# airu-schematic-pi.net
KiCad netlist of a schematic drawn in EAGLE
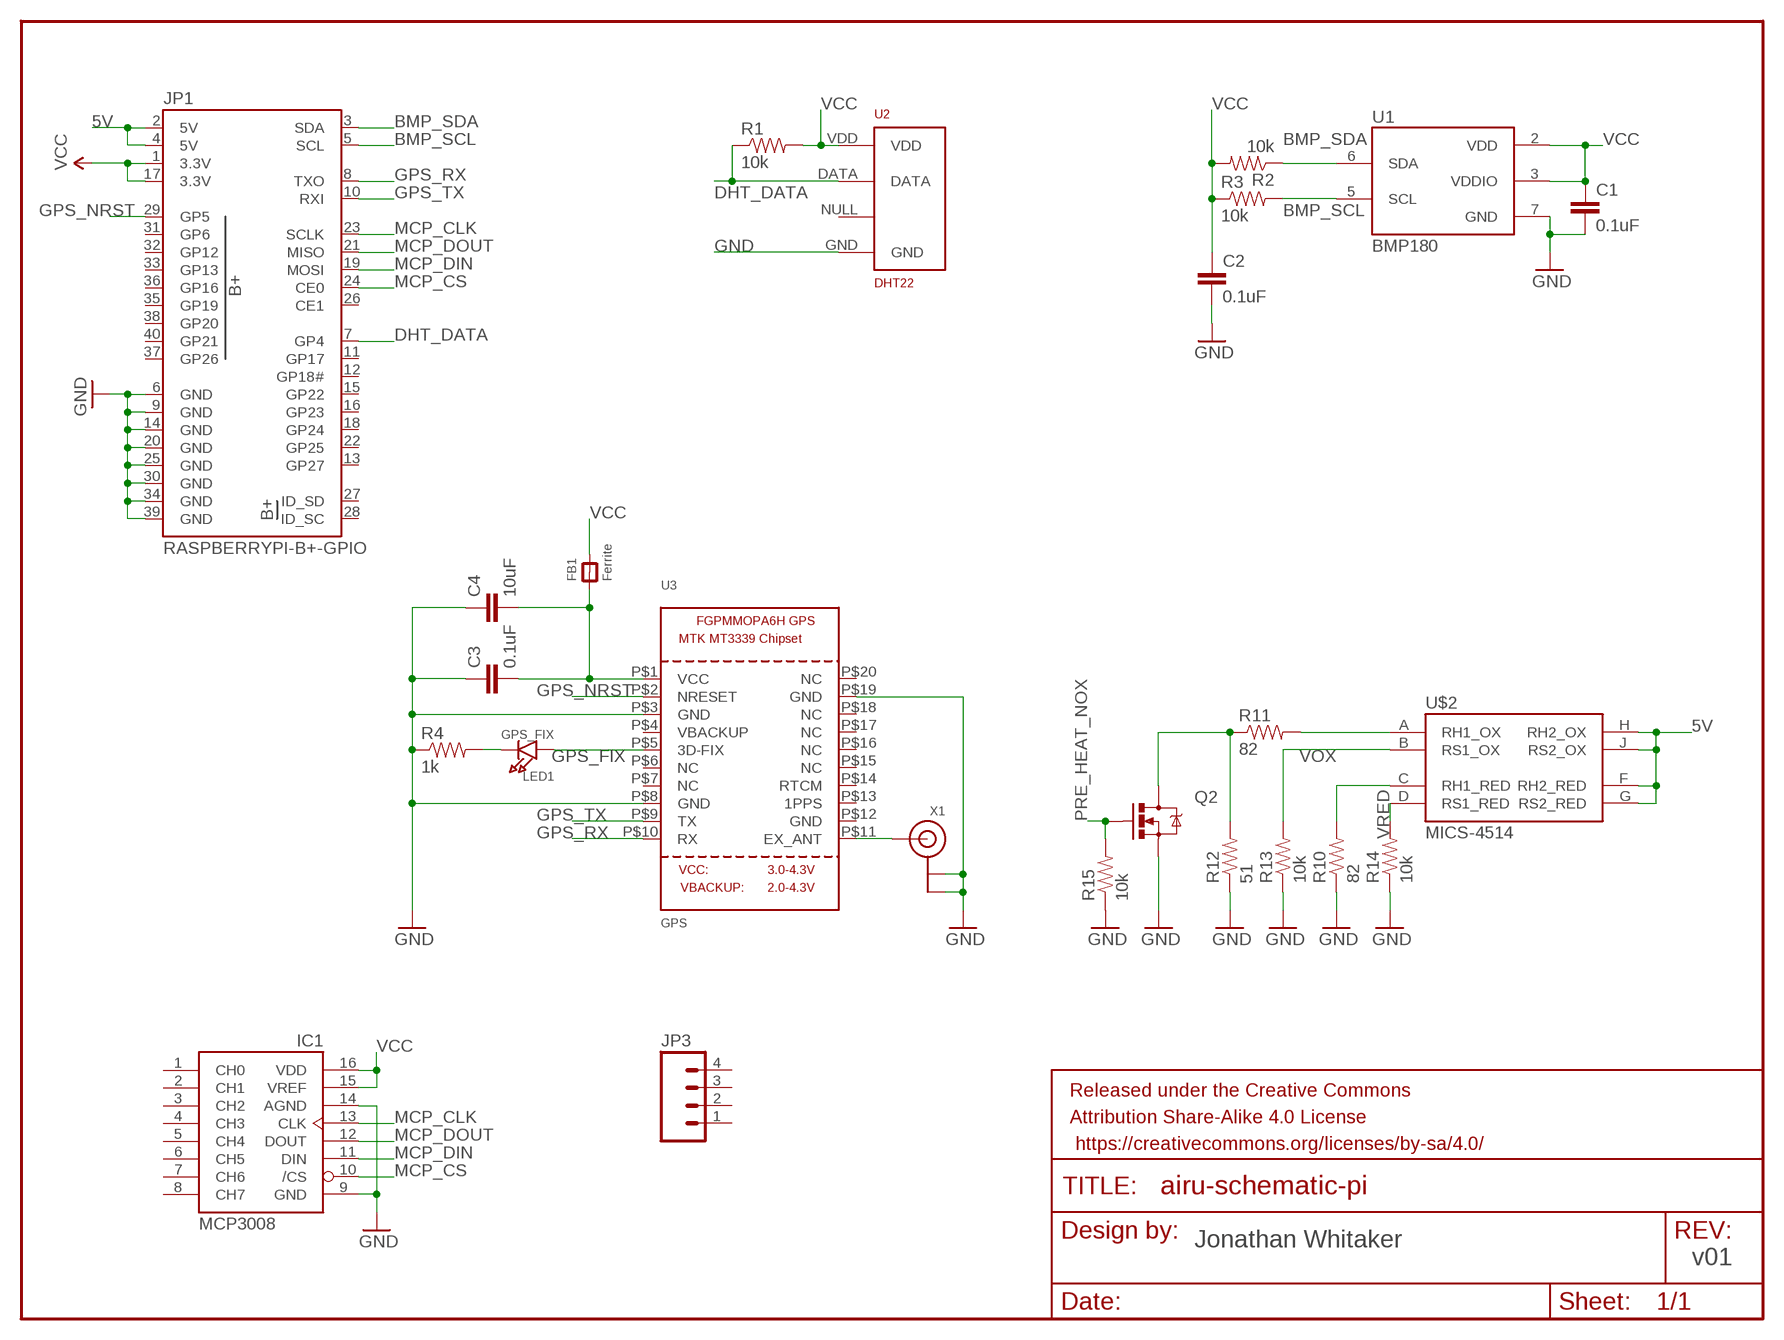
[diagram p0: schematic, sheet 1]

(export (version "E")
  (design (tool "Eeschema 10.0.6"))
  (components
    (comp (ref "C1")
      (value "0.1uF")
      (footprint "eagle-import:1206")
      (libsource (lib "eagle-import") (part "CAP1206"))
    )
    (comp (ref "C2")
      (value "0.1uF")
      (footprint "eagle-import:1206")
      (libsource (lib "eagle-import") (part "CAP1206"))
    )
    (comp (ref "C3")
      (value "0.1uF")
      (footprint "eagle-import:1206")
      (libsource (lib "eagle-import") (part "CAP1206"))
    )
    (comp (ref "C4")
      (value "10uF")
      (footprint "eagle-import:1206")
      (libsource (lib "eagle-import") (part "CAP1206"))
    )
    (comp (ref "FB1")
      (value "Ferrite")
      (footprint "eagle-import:0805")
      (libsource (lib "eagle-import") (part "FERRITE0805"))
    )
    (comp (ref "FRAME1")
      (value "FRAME-LETTER")
      (footprint "eagle-import:CREATIVE_COMMONS")
      (fields
        (field (name "DESIGNER") "Jonathan Whitaker")
        (field (name "VERSION") "v01")
        (field (name "DESIGNER_1") "Jonathan Whitaker")
      )
      (libsource (lib "eagle-import") (part "FRAME-LETTER"))
    )
    (comp (ref "IC1")
      (value "MCP3008")
      (footprint "eagle-import:DIL16")
      (libsource (lib "eagle-import") (part "MCP3008"))
    )
    (comp (ref "JP1")
      (value "RASPBERRYPI-B+-GPIO")
      (footprint "eagle-import:2X20-SHROUDED")
      (libsource (lib "eagle-import") (part "RASPBERRYPI-B+-GPIO"))
    )
    (comp (ref "JP3")
      (value "M04JST-PTH")
      (footprint "eagle-import:JST-4-PTH")
      (libsource (lib "eagle-import") (part "M04JST-PTH"))
    )
    (comp (ref "LED1")
      (value "GPS_FIX")
      (footprint "eagle-import:CHIPLED_1206")
      (libsource (lib "eagle-import") (part "LED1206"))
    )
    (comp (ref "Q2")
      (value "MOSFET-NCHANNELAO3404A")
      (footprint "eagle-import:SOT23-3")
      (libsource (lib "eagle-import") (part "MOSFET-NCHANNELAO3404A"))
    )
    (comp (ref "R1")
      (value "10k")
      (footprint "eagle-import:1206")
      (libsource (lib "eagle-import") (part "RESISTOR1206"))
    )
    (comp (ref "R2")
      (value "10k")
      (footprint "eagle-import:1206")
      (libsource (lib "eagle-import") (part "RESISTOR1206"))
    )
    (comp (ref "R3")
      (value "10k")
      (footprint "eagle-import:1206")
      (libsource (lib "eagle-import") (part "RESISTOR1206"))
    )
    (comp (ref "R4")
      (value "1k")
      (footprint "eagle-import:1206")
      (libsource (lib "eagle-import") (part "RESISTOR1206"))
    )
    (comp (ref "R10")
      (value "82")
      (footprint "eagle-import:1206")
      (libsource (lib "eagle-import") (part "RESISTOR1206"))
    )
    (comp (ref "R11")
      (value "82")
      (footprint "eagle-import:1206")
      (libsource (lib "eagle-import") (part "RESISTOR1206"))
    )
    (comp (ref "R12")
      (value "51")
      (footprint "eagle-import:1206")
      (libsource (lib "eagle-import") (part "RESISTOR1206"))
    )
    (comp (ref "R13")
      (value "10k")
      (footprint "eagle-import:1206")
      (libsource (lib "eagle-import") (part "RESISTOR1206"))
    )
    (comp (ref "R14")
      (value "10k")
      (footprint "eagle-import:1206")
      (libsource (lib "eagle-import") (part "RESISTOR1206"))
    )
    (comp (ref "R15")
      (value "10k")
      (footprint "eagle-import:1206")
      (libsource (lib "eagle-import") (part "RESISTOR1206"))
    )
    (comp (ref "U$2")
      (value "MICS-4514")
      (footprint "eagle-import:MICS_10-SMD")
      (libsource (lib "eagle-import") (part "MICS-4514"))
    )
    (comp (ref "U1")
      (value "BMP180")
      (footprint "eagle-import:BMP180")
      (libsource (lib "eagle-import") (part "BMP180"))
    )
    (comp (ref "U2")
      (value "DHT22")
      (footprint "eagle-import:RHT03_DHT-22")
      (libsource (lib "eagle-import") (part "RHT03_DHT-22_AM2302"))
    )
    (comp (ref "U3")
      (value "GPS")
      (footprint "eagle-import:FGPMMOPA6H")
      (libsource (lib "eagle-import") (part "GPS_FGPMMOPA6H"))
    )
    (comp (ref "X1")
      (value "ANTENNA_U.FL")
      (footprint "eagle-import:U.FL")
      (libsource (lib "eagle-import") (part "ANTENNA_U.FL"))
    )
  )
  (nets
    (net (code "1") (name "/5V") (class "Default")
      (node (ref "JP1") (pin "2") (pinfunction "5V_2") (pintype "power_in"))
      (node (ref "JP1") (pin "4") (pinfunction "5V_4") (pintype "power_in"))
      (node (ref "U$2") (pin "F") (pinfunction "RH2_RED_F") (pintype "bidirectional"))
      (node (ref "U$2") (pin "G") (pinfunction "RS2_RED_G") (pintype "bidirectional"))
      (node (ref "U$2") (pin "H") (pinfunction "RH2_OX_H") (pintype "bidirectional"))
      (node (ref "U$2") (pin "J") (pinfunction "RS2_OX_J") (pintype "bidirectional"))
    )
    (net (code "2") (name "/BMP_SCL") (class "Default")
      (node (ref "JP1") (pin "5") (pinfunction "SCL_5") (pintype "bidirectional"))
      (node (ref "R3") (pin "2") (pinfunction "2_2") (pintype "passive"))
      (node (ref "U1") (pin "5") (pinfunction "SCL_5") (pintype "input"))
    )
    (net (code "3") (name "/BMP_SDA") (class "Default")
      (node (ref "JP1") (pin "3") (pinfunction "SDA_3") (pintype "bidirectional"))
      (node (ref "R2") (pin "1") (pinfunction "1_1") (pintype "passive"))
      (node (ref "U1") (pin "6") (pinfunction "SDA_6") (pintype "bidirectional"))
    )
    (net (code "4") (name "/DHT_DATA") (class "Default")
      (node (ref "JP1") (pin "7") (pinfunction "GP4_7") (pintype "bidirectional"))
      (node (ref "R1") (pin "1") (pinfunction "1_1") (pintype "passive"))
      (node (ref "U2") (pin "DATA") (pinfunction "DATA_DATA") (pintype "bidirectional"))
    )
    (net (code "5") (name "/GPS_FIX") (class "Default")
      (node (ref "LED1") (pin "A") (pinfunction "A_A") (pintype "passive"))
      (node (ref "U3") (pin "P$5") (pinfunction "3D-FIX_P$5") (pintype "bidirectional"))
    )
    (net (code "6") (name "/GPS_NRST") (class "Default")
      (node (ref "JP1") (pin "29") (pinfunction "GP5_29") (pintype "bidirectional"))
      (node (ref "U3") (pin "P$2") (pinfunction "NRESET_P$2") (pintype "bidirectional"))
    )
    (net (code "7") (name "/GPS_RX") (class "Default")
      (node (ref "JP1") (pin "8") (pinfunction "TXO_8") (pintype "output"))
      (node (ref "U3") (pin "P$10") (pinfunction "RX_P$10") (pintype "bidirectional"))
    )
    (net (code "8") (name "/GPS_TX") (class "Default")
      (node (ref "JP1") (pin "10") (pinfunction "RXI_10") (pintype "input"))
      (node (ref "U3") (pin "P$9") (pinfunction "TX_P$9") (pintype "bidirectional"))
    )
    (net (code "9") (name "/MCP_CLK") (class "Default")
      (node (ref "IC1") (pin "13") (pinfunction "CLK_13") (pintype "input"))
      (node (ref "JP1") (pin "23") (pinfunction "SCLK_23") (pintype "output"))
    )
    (net (code "10") (name "/MCP_CS") (class "Default")
      (node (ref "IC1") (pin "10") (pinfunction "/CS_10") (pintype "input"))
      (node (ref "JP1") (pin "24") (pinfunction "CE0_24") (pintype "output"))
    )
    (net (code "11") (name "/MCP_DIN") (class "Default")
      (node (ref "IC1") (pin "11") (pinfunction "DIN_11") (pintype "input"))
      (node (ref "JP1") (pin "19") (pinfunction "MOSI_19") (pintype "output"))
    )
    (net (code "12") (name "/MCP_DOUT") (class "Default")
      (node (ref "IC1") (pin "12") (pinfunction "DOUT_12") (pintype "output"))
      (node (ref "JP1") (pin "21") (pinfunction "MISO_21") (pintype "input"))
    )
    (net (code "13") (name "/PRE_HEAT_NOX") (class "Default")
      (node (ref "Q2") (pin "1") (pinfunction "G_1") (pintype "passive"))
      (node (ref "R15") (pin "2") (pinfunction "2_2") (pintype "passive"))
    )
    (net (code "14") (name "/VOX") (class "Default")
      (node (ref "R13") (pin "2") (pinfunction "2_2") (pintype "passive"))
      (node (ref "U$2") (pin "B") (pinfunction "RS1_OX_B") (pintype "bidirectional"))
    )
    (net (code "15") (name "/VRED") (class "Default")
      (node (ref "R14") (pin "2") (pinfunction "2_2") (pintype "passive"))
      (node (ref "U$2") (pin "D") (pinfunction "RS1_RED_D") (pintype "bidirectional"))
    )
    (net (code "16") (name "GND") (class "Default")
      (node (ref "C1") (pin "2") (pinfunction "2_2") (pintype "passive"))
      (node (ref "C2") (pin "2") (pinfunction "2_2") (pintype "passive"))
      (node (ref "C3") (pin "1") (pinfunction "1_1") (pintype "passive"))
      (node (ref "C4") (pin "1") (pinfunction "1_1") (pintype "passive"))
      (node (ref "IC1") (pin "14") (pinfunction "AGND_14") (pintype "power_in"))
      (node (ref "IC1") (pin "9") (pinfunction "GND_9") (pintype "power_in"))
      (node (ref "JP1") (pin "14") (pinfunction "GND_14") (pintype "power_in"))
      (node (ref "JP1") (pin "20") (pinfunction "GND_20") (pintype "power_in"))
      (node (ref "JP1") (pin "25") (pinfunction "GND_25") (pintype "power_in"))
      (node (ref "JP1") (pin "30") (pinfunction "GND_30") (pintype "power_in"))
      (node (ref "JP1") (pin "34") (pinfunction "GND_34") (pintype "power_in"))
      (node (ref "JP1") (pin "39") (pinfunction "GND_39") (pintype "power_in"))
      (node (ref "JP1") (pin "6") (pinfunction "GND_6") (pintype "power_in"))
      (node (ref "JP1") (pin "9") (pinfunction "GND_9") (pintype "power_in"))
      (node (ref "Q2") (pin "2") (pinfunction "S_2") (pintype "passive"))
      (node (ref "R10") (pin "1") (pinfunction "1_1") (pintype "passive"))
      (node (ref "R12") (pin "1") (pinfunction "1_1") (pintype "passive"))
      (node (ref "R13") (pin "1") (pinfunction "1_1") (pintype "passive"))
      (node (ref "R14") (pin "1") (pinfunction "1_1") (pintype "passive"))
      (node (ref "R15") (pin "1") (pinfunction "1_1") (pintype "passive"))
      (node (ref "R4") (pin "1") (pinfunction "1_1") (pintype "passive"))
      (node (ref "U1") (pin "7") (pinfunction "GND_7") (pintype "power_in"))
      (node (ref "U2") (pin "GND") (pinfunction "GND_GND") (pintype "power_in"))
      (node (ref "U3") (pin "P$19") (pinfunction "GND_P$19") (pintype "bidirectional"))
      (node (ref "U3") (pin "P$3") (pinfunction "GND_P$3") (pintype "bidirectional"))
      (node (ref "U3") (pin "P$8") (pinfunction "GND_P$8") (pintype "bidirectional"))
      (node (ref "X1") (pin "1") (pinfunction "GND_1") (pintype "passive"))
      (node (ref "X1") (pin "2") (pinfunction "GND_2") (pintype "passive"))
    )
    (net (code "17") (name "Net-(FB1-P$1)") (class "Default")
      (node (ref "C3") (pin "2") (pinfunction "2_2") (pintype "passive"))
      (node (ref "C4") (pin "2") (pinfunction "2_2") (pintype "passive"))
      (node (ref "FB1") (pin "1") (pinfunction "P$1_1") (pintype "passive"))
      (node (ref "U3") (pin "P$1") (pinfunction "VCC_P$1") (pintype "bidirectional"))
    )
    (net (code "18") (name "Net-(LED1-PadC)") (class "Default")
      (node (ref "LED1") (pin "C") (pinfunction "C_C") (pintype "passive"))
      (node (ref "R4") (pin "2") (pinfunction "2_2") (pintype "passive"))
    )
    (net (code "19") (name "Net-(Q2-D)") (class "Default")
      (node (ref "Q2") (pin "3") (pinfunction "D_3") (pintype "passive"))
      (node (ref "R11") (pin "1") (pinfunction "1_1") (pintype "passive"))
      (node (ref "R12") (pin "2") (pinfunction "2_2") (pintype "passive"))
    )
    (net (code "20") (name "Net-(U$2-RH1_OX)") (class "Default")
      (node (ref "R11") (pin "2") (pinfunction "2_2") (pintype "passive"))
      (node (ref "U$2") (pin "A") (pinfunction "RH1_OX_A") (pintype "bidirectional"))
    )
    (net (code "21") (name "Net-(U$2-RH1_RED)") (class "Default")
      (node (ref "R10") (pin "2") (pinfunction "2_2") (pintype "passive"))
      (node (ref "U$2") (pin "C") (pinfunction "RH1_RED_C") (pintype "bidirectional"))
    )
    (net (code "22") (name "Net-(U3-EX_ANT)") (class "Default")
      (node (ref "U3") (pin "P$11") (pinfunction "EX_ANT_P$11") (pintype "bidirectional"))
      (node (ref "X1") (pin "3") (pinfunction "SIGNAL_3") (pintype "passive"))
    )
    (net (code "23") (name "VCC") (class "Default")
      (node (ref "C1") (pin "1") (pinfunction "1_1") (pintype "passive"))
      (node (ref "C2") (pin "1") (pinfunction "1_1") (pintype "passive"))
      (node (ref "FB1") (pin "2") (pinfunction "P$2_2") (pintype "passive"))
      (node (ref "IC1") (pin "15") (pinfunction "VREF_15") (pintype "input"))
      (node (ref "IC1") (pin "16") (pinfunction "VDD_16") (pintype "power_in"))
      (node (ref "JP1") (pin "1") (pinfunction "3.3V_1") (pintype "power_in"))
      (node (ref "JP1") (pin "17") (pinfunction "3.3V_17") (pintype "power_in"))
      (node (ref "R1") (pin "2") (pinfunction "2_2") (pintype "passive"))
      (node (ref "R2") (pin "2") (pinfunction "2_2") (pintype "passive"))
      (node (ref "R3") (pin "1") (pinfunction "1_1") (pintype "passive"))
      (node (ref "U1") (pin "2") (pinfunction "VDD_2") (pintype "power_in"))
      (node (ref "U1") (pin "3") (pinfunction "VDDIO_3") (pintype "power_in"))
      (node (ref "U2") (pin "VDD") (pinfunction "VDD_VDD") (pintype "power_in"))
    )
    (net (code "24") (name "unconnected-(IC1-CH0-Pad1)") (class "Default")
      (node (ref "IC1") (pin "1") (pinfunction "CH0_1") (pintype "input"))
    )
    (net (code "25") (name "unconnected-(IC1-CH1-Pad2)") (class "Default")
      (node (ref "IC1") (pin "2") (pinfunction "CH1_2") (pintype "input"))
    )
    (net (code "26") (name "unconnected-(IC1-CH2-Pad3)") (class "Default")
      (node (ref "IC1") (pin "3") (pinfunction "CH2_3") (pintype "input"))
    )
    (net (code "27") (name "unconnected-(IC1-CH3-Pad4)") (class "Default")
      (node (ref "IC1") (pin "4") (pinfunction "CH3_4") (pintype "input"))
    )
    (net (code "28") (name "unconnected-(IC1-CH4-Pad5)") (class "Default")
      (node (ref "IC1") (pin "5") (pinfunction "CH4_5") (pintype "input"))
    )
    (net (code "29") (name "unconnected-(IC1-CH5-Pad6)") (class "Default")
      (node (ref "IC1") (pin "6") (pinfunction "CH5_6") (pintype "input"))
    )
    (net (code "30") (name "unconnected-(IC1-CH6-Pad7)") (class "Default")
      (node (ref "IC1") (pin "7") (pinfunction "CH6_7") (pintype "input"))
    )
    (net (code "31") (name "unconnected-(IC1-CH7-Pad8)") (class "Default")
      (node (ref "IC1") (pin "8") (pinfunction "CH7_8") (pintype "input"))
    )
    (net (code "32") (name "unconnected-(JP1-CE1-Pad26)") (class "Default")
      (node (ref "JP1") (pin "26") (pinfunction "CE1_26") (pintype "output"))
    )
    (net (code "33") (name "unconnected-(JP1-GP6-Pad31)") (class "Default")
      (node (ref "JP1") (pin "31") (pinfunction "GP6_31") (pintype "bidirectional"))
    )
    (net (code "34") (name "unconnected-(JP1-GP12-Pad32)") (class "Default")
      (node (ref "JP1") (pin "32") (pinfunction "GP12_32") (pintype "bidirectional"))
    )
    (net (code "35") (name "unconnected-(JP1-GP13-Pad33)") (class "Default")
      (node (ref "JP1") (pin "33") (pinfunction "GP13_33") (pintype "bidirectional"))
    )
    (net (code "36") (name "unconnected-(JP1-GP16-Pad36)") (class "Default")
      (node (ref "JP1") (pin "36") (pinfunction "GP16_36") (pintype "bidirectional"))
    )
    (net (code "37") (name "unconnected-(JP1-GP17-Pad11)") (class "Default")
      (node (ref "JP1") (pin "11") (pinfunction "GP17_11") (pintype "bidirectional"))
    )
    (net (code "38") (name "unconnected-(JP1-GP18#-Pad12)") (class "Default")
      (node (ref "JP1") (pin "12") (pinfunction "GP18#_12") (pintype "bidirectional"))
    )
    (net (code "39") (name "unconnected-(JP1-GP19-Pad35)") (class "Default")
      (node (ref "JP1") (pin "35") (pinfunction "GP19_35") (pintype "bidirectional"))
    )
    (net (code "40") (name "unconnected-(JP1-GP20-Pad38)") (class "Default")
      (node (ref "JP1") (pin "38") (pinfunction "GP20_38") (pintype "bidirectional"))
    )
    (net (code "41") (name "unconnected-(JP1-GP21-Pad40)") (class "Default")
      (node (ref "JP1") (pin "40") (pinfunction "GP21_40") (pintype "bidirectional"))
    )
    (net (code "42") (name "unconnected-(JP1-GP22-Pad15)") (class "Default")
      (node (ref "JP1") (pin "15") (pinfunction "GP22_15") (pintype "bidirectional"))
    )
    (net (code "43") (name "unconnected-(JP1-GP23-Pad16)") (class "Default")
      (node (ref "JP1") (pin "16") (pinfunction "GP23_16") (pintype "bidirectional"))
    )
    (net (code "44") (name "unconnected-(JP1-GP24-Pad18)") (class "Default")
      (node (ref "JP1") (pin "18") (pinfunction "GP24_18") (pintype "bidirectional"))
    )
    (net (code "45") (name "unconnected-(JP1-GP25-Pad22)") (class "Default")
      (node (ref "JP1") (pin "22") (pinfunction "GP25_22") (pintype "bidirectional"))
    )
    (net (code "46") (name "unconnected-(JP1-GP26-Pad37)") (class "Default")
      (node (ref "JP1") (pin "37") (pinfunction "GP26_37") (pintype "bidirectional"))
    )
    (net (code "47") (name "unconnected-(JP1-GP27-Pad13)") (class "Default")
      (node (ref "JP1") (pin "13") (pinfunction "GP27_13") (pintype "bidirectional"))
    )
    (net (code "48") (name "unconnected-(JP1-ID_SC-Pad28)") (class "Default")
      (node (ref "JP1") (pin "28") (pinfunction "ID_SC_28") (pintype "bidirectional"))
    )
    (net (code "49") (name "unconnected-(JP1-ID_SD-Pad27)") (class "Default")
      (node (ref "JP1") (pin "27") (pinfunction "ID_SD_27") (pintype "bidirectional"))
    )
    (net (code "50") (name "unconnected-(JP3-Pad1)") (class "Default")
      (node (ref "JP3") (pin "1") (pinfunction "1_1") (pintype "passive"))
    )
    (net (code "51") (name "unconnected-(JP3-Pad2)") (class "Default")
      (node (ref "JP3") (pin "2") (pinfunction "2_2") (pintype "passive"))
    )
    (net (code "52") (name "unconnected-(JP3-Pad3)") (class "Default")
      (node (ref "JP3") (pin "3") (pinfunction "3_3") (pintype "passive"))
    )
    (net (code "53") (name "unconnected-(JP3-Pad4)") (class "Default")
      (node (ref "JP3") (pin "4") (pinfunction "4_4") (pintype "passive"))
    )
    (net (code "54") (name "unconnected-(U2-PadNULL)") (class "Default")
      (node (ref "U2") (pin "NULL") (pinfunction "NULL_NULL") (pintype "no_connect"))
    )
    (net (code "55") (name "unconnected-(U3-1PPS-PadP$13)") (class "Default")
      (node (ref "U3") (pin "P$13") (pinfunction "1PPS_P$13") (pintype "bidirectional"))
    )
    (net (code "56") (name "unconnected-(U3-GND-PadP$12)") (class "Default")
      (node (ref "U3") (pin "P$12") (pinfunction "GND_P$12") (pintype "bidirectional"))
    )
    (net (code "57") (name "unconnected-(U3-NC-PadP$6)") (class "Default")
      (node (ref "U3") (pin "P$6") (pinfunction "NC_P$6") (pintype "bidirectional"))
    )
    (net (code "58") (name "unconnected-(U3-NC-PadP$7)") (class "Default")
      (node (ref "U3") (pin "P$7") (pinfunction "NC_P$7") (pintype "bidirectional"))
    )
    (net (code "59") (name "unconnected-(U3-NC-PadP$15)") (class "Default")
      (node (ref "U3") (pin "P$15") (pinfunction "NC_P$15") (pintype "bidirectional"))
    )
    (net (code "60") (name "unconnected-(U3-NC-PadP$16)") (class "Default")
      (node (ref "U3") (pin "P$16") (pinfunction "NC_P$16") (pintype "bidirectional"))
    )
    (net (code "61") (name "unconnected-(U3-NC-PadP$17)") (class "Default")
      (node (ref "U3") (pin "P$17") (pinfunction "NC_P$17") (pintype "bidirectional"))
    )
    (net (code "62") (name "unconnected-(U3-NC-PadP$18)") (class "Default")
      (node (ref "U3") (pin "P$18") (pinfunction "NC_P$18") (pintype "bidirectional"))
    )
    (net (code "63") (name "unconnected-(U3-NC-PadP$20)") (class "Default")
      (node (ref "U3") (pin "P$20") (pinfunction "NC_P$20") (pintype "bidirectional"))
    )
    (net (code "64") (name "unconnected-(U3-RTCM-PadP$14)") (class "Default")
      (node (ref "U3") (pin "P$14") (pinfunction "RTCM_P$14") (pintype "bidirectional"))
    )
    (net (code "65") (name "unconnected-(U3-VBACKUP-PadP$4)") (class "Default")
      (node (ref "U3") (pin "P$4") (pinfunction "VBACKUP_P$4") (pintype "bidirectional"))
    )
  )
)
